# 13thISE_ver11.net
KiCad netlist of a schematic drawn in EAGLE
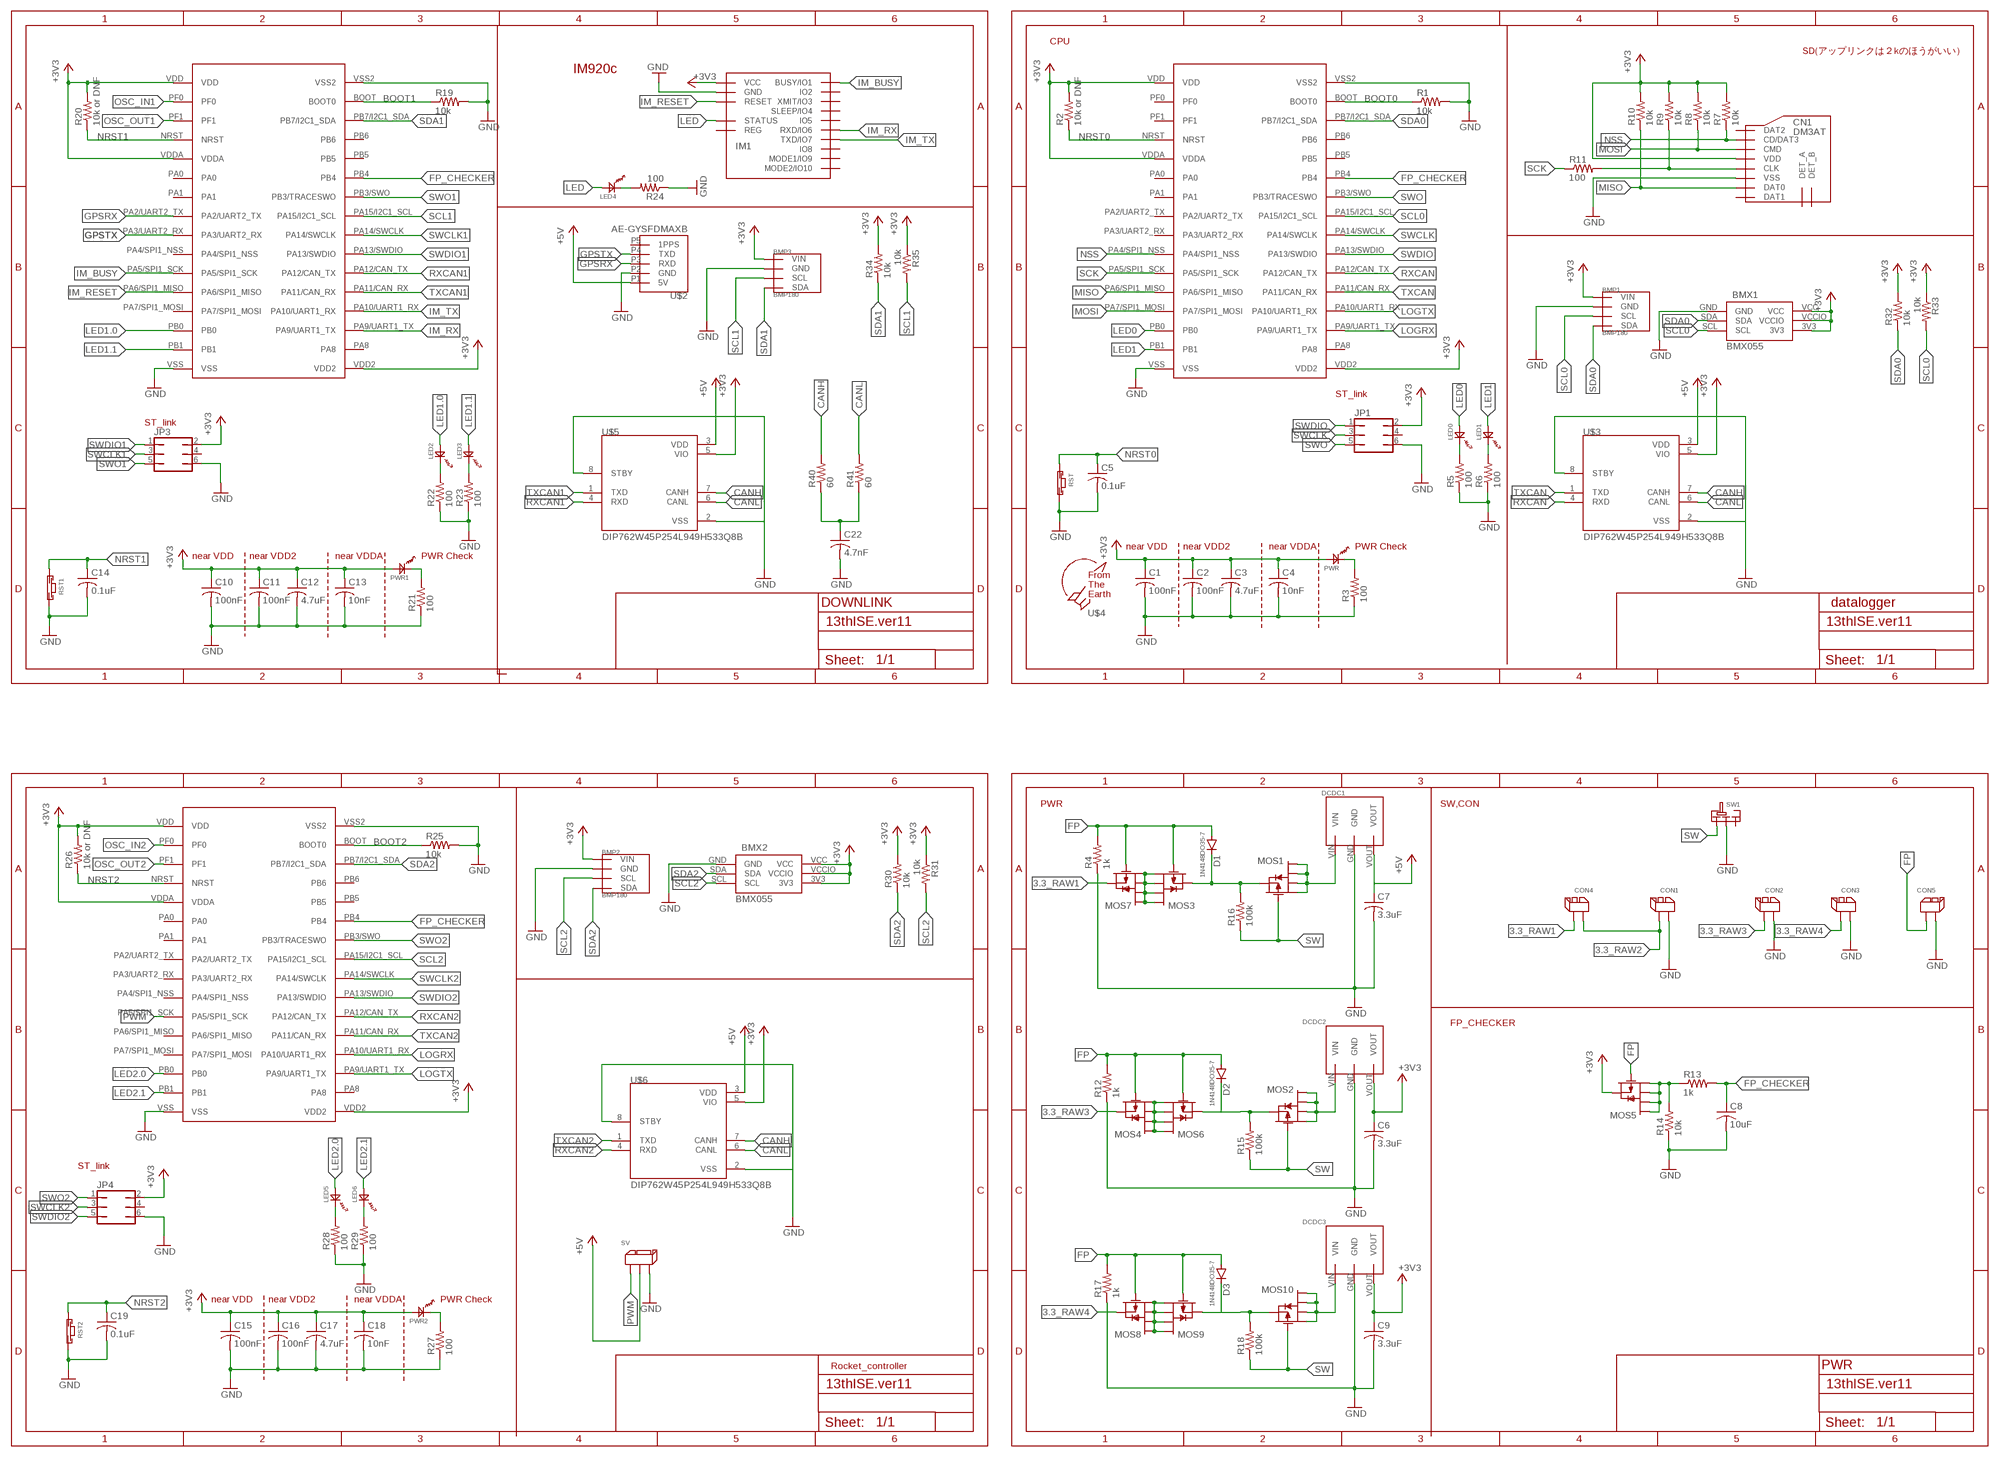
[diagram p0: schematic, sheet 1]

(export (version "E")
  (design (tool "Eeschema 10.0.6"))
  (components
    (comp (ref "BMP1")
      (value "BMP180")
      (footprint "eagle-import:GY-68")
      (libsource (lib "eagle-import") (part "BMP180"))
    )
    (comp (ref "BMP2")
      (value "BMP180")
      (footprint "eagle-import:GY-68")
      (libsource (lib "eagle-import") (part "BMP180"))
    )
    (comp (ref "BMP3")
      (value "BMP180")
      (footprint "eagle-import:GY-68")
      (libsource (lib "eagle-import") (part "BMP180"))
    )
    (comp (ref "BMX1")
      (value "BMX055")
      (footprint "eagle-import:BMX055")
      (libsource (lib "eagle-import") (part "BMX055"))
    )
    (comp (ref "BMX2")
      (value "BMX055")
      (footprint "eagle-import:BMX055")
      (libsource (lib "eagle-import") (part "BMX055"))
    )
    (comp (ref "C1")
      (value "100nF")
      (footprint "eagle-import:C1608")
      (libsource (lib "eagle-import") (part "C-USC1608"))
    )
    (comp (ref "C2")
      (value "100nF")
      (footprint "eagle-import:C1608")
      (libsource (lib "eagle-import") (part "C-USC1608"))
    )
    (comp (ref "C3")
      (value "4.7uF")
      (footprint "eagle-import:C1608")
      (libsource (lib "eagle-import") (part "C-USC1608"))
    )
    (comp (ref "C4")
      (value "10nF")
      (footprint "eagle-import:C1608")
      (libsource (lib "eagle-import") (part "C-USC1608"))
    )
    (comp (ref "C5")
      (value "0.1uF")
      (footprint "eagle-import:C1608")
      (libsource (lib "eagle-import") (part "C-USC1608"))
    )
    (comp (ref "C6")
      (value "3.3uF")
      (footprint "eagle-import:C0603")
      (libsource (lib "eagle-import") (part "C-USC0603"))
    )
    (comp (ref "C7")
      (value "3.3uF")
      (footprint "eagle-import:C0603")
      (libsource (lib "eagle-import") (part "C-USC0603"))
    )
    (comp (ref "C8")
      (value "10uF")
      (footprint "eagle-import:C0603")
      (libsource (lib "eagle-import") (part "C-USC0603"))
    )
    (comp (ref "C9")
      (value "3.3uF")
      (footprint "eagle-import:C0603")
      (libsource (lib "eagle-import") (part "C-USC0603"))
    )
    (comp (ref "C10")
      (value "100nF")
      (footprint "eagle-import:C1608")
      (libsource (lib "eagle-import") (part "C-USC1608"))
    )
    (comp (ref "C11")
      (value "100nF")
      (footprint "eagle-import:C1608")
      (libsource (lib "eagle-import") (part "C-USC1608"))
    )
    (comp (ref "C12")
      (value "4.7uF")
      (footprint "eagle-import:C1608")
      (libsource (lib "eagle-import") (part "C-USC1608"))
    )
    (comp (ref "C13")
      (value "10nF")
      (footprint "eagle-import:C1608")
      (libsource (lib "eagle-import") (part "C-USC1608"))
    )
    (comp (ref "C14")
      (value "0.1uF")
      (footprint "eagle-import:C1608")
      (libsource (lib "eagle-import") (part "C-USC1608"))
    )
    (comp (ref "C15")
      (value "100nF")
      (footprint "eagle-import:C1608")
      (libsource (lib "eagle-import") (part "C-USC1608"))
    )
    (comp (ref "C16")
      (value "100nF")
      (footprint "eagle-import:C1608")
      (libsource (lib "eagle-import") (part "C-USC1608"))
    )
    (comp (ref "C17")
      (value "4.7uF")
      (footprint "eagle-import:C1608")
      (libsource (lib "eagle-import") (part "C-USC1608"))
    )
    (comp (ref "C18")
      (value "10nF")
      (footprint "eagle-import:C1608")
      (libsource (lib "eagle-import") (part "C-USC1608"))
    )
    (comp (ref "C19")
      (value "0.1uF")
      (footprint "eagle-import:C1608")
      (libsource (lib "eagle-import") (part "C-USC1608"))
    )
    (comp (ref "C22")
      (value "4.7nF")
      (footprint "eagle-import:C0603")
      (libsource (lib "eagle-import") (part "C-USC0603"))
    )
    (comp (ref "CN1")
      (value "DM3AT")
      (footprint "eagle-import:DM3AT")
      (libsource (lib "eagle-import") (part "DM3AT"))
    )
    (comp (ref "CON1")
      (value "2PIN")
      (footprint "eagle-import:2PIN")
      (libsource (lib "eagle-import") (part "2PIN"))
    )
    (comp (ref "CON2")
      (value "2PIN")
      (footprint "eagle-import:2PIN")
      (libsource (lib "eagle-import") (part "2PIN"))
    )
    (comp (ref "CON3")
      (value "2PIN")
      (footprint "eagle-import:2PIN")
      (libsource (lib "eagle-import") (part "2PIN"))
    )
    (comp (ref "CON4")
      (value "2PIN")
      (footprint "eagle-import:2PIN")
      (libsource (lib "eagle-import") (part "2PIN"))
    )
    (comp (ref "CON5")
      (value "2PIN")
      (footprint "eagle-import:2PIN")
      (libsource (lib "eagle-import") (part "2PIN"))
    )
    (comp (ref "D1")
      (value "1N4148DO35-7")
      (footprint "eagle-import:DO35-7")
      (libsource (lib "eagle-import") (part "1N4148DO35-7"))
    )
    (comp (ref "D2")
      (value "1N4148DO35-7")
      (footprint "eagle-import:DO35-7")
      (libsource (lib "eagle-import") (part "1N4148DO35-7"))
    )
    (comp (ref "D3")
      (value "1N4148DO35-7")
      (footprint "eagle-import:DO35-7")
      (libsource (lib "eagle-import") (part "1N4148DO35-7"))
    )
    (comp (ref "DCDC1")
      (value "5V1A_M78AR05-1")
      (footprint "eagle-import:5V1A_M78AR05-1")
      (libsource (lib "eagle-import") (part "5V1A_M78AR05-1"))
    )
    (comp (ref "DCDC2")
      (value "3.3V1A_M78AR033-1")
      (footprint "eagle-import:3.3V1A_M78AR033-1")
      (libsource (lib "eagle-import") (part "3.3V1A_M78AR033-1"))
    )
    (comp (ref "DCDC3")
      (value "3.3V1A_M78AR033-1")
      (footprint "eagle-import:3.3V1A_M78AR033-1")
      (libsource (lib "eagle-import") (part "3.3V1A_M78AR033-1"))
    )
    (comp (ref "IM1")
      (value "IM920_IM920C")
      (footprint "eagle-import:IM920_IM920C")
      (libsource (lib "eagle-import") (part "IM920_IM920C"))
    )
    (comp (ref "JP1")
      (value "JP3Q")
      (footprint "eagle-import:JP3Q")
      (libsource (lib "eagle-import") (part "JP3Q"))
    )
    (comp (ref "JP3")
      (value "JP3Q")
      (footprint "eagle-import:JP3Q")
      (libsource (lib "eagle-import") (part "JP3Q"))
    )
    (comp (ref "JP4")
      (value "JP3Q")
      (footprint "eagle-import:JP3Q")
      (libsource (lib "eagle-import") (part "JP3Q"))
    )
    (comp (ref "LED0")
      (value "OSXX1608C1A")
      (footprint "eagle-import:OSXX1608C1A")
      (libsource (lib "eagle-import") (part "OSXX1608C1A"))
    )
    (comp (ref "LED1")
      (value "OSXX1608C1A")
      (footprint "eagle-import:OSXX1608C1A")
      (libsource (lib "eagle-import") (part "OSXX1608C1A"))
    )
    (comp (ref "LED2")
      (value "OSXX1608C1A")
      (footprint "eagle-import:OSXX1608C1A")
      (libsource (lib "eagle-import") (part "OSXX1608C1A"))
    )
    (comp (ref "LED3")
      (value "OSXX1608C1A")
      (footprint "eagle-import:OSXX1608C1A")
      (libsource (lib "eagle-import") (part "OSXX1608C1A"))
    )
    (comp (ref "LED4")
      (value "OSXX1608C1A")
      (footprint "eagle-import:OSXX1608C1A")
      (libsource (lib "eagle-import") (part "OSXX1608C1A"))
    )
    (comp (ref "LED5")
      (value "OSXX1608C1A")
      (footprint "eagle-import:OSXX1608C1A")
      (libsource (lib "eagle-import") (part "OSXX1608C1A"))
    )
    (comp (ref "LED6")
      (value "OSXX1608C1A")
      (footprint "eagle-import:OSXX1608C1A")
      (libsource (lib "eagle-import") (part "OSXX1608C1A"))
    )
    (comp (ref "MOS1")
      (value "PCH_SSM6J808R")
      (footprint "eagle-import:SSM6J808R")
      (libsource (lib "eagle-import") (part "PCH_SSM6J808R"))
    )
    (comp (ref "MOS2")
      (value "PCH_SSM6J808R")
      (footprint "eagle-import:SSM6J808R")
      (libsource (lib "eagle-import") (part "PCH_SSM6J808R"))
    )
    (comp (ref "MOS3")
      (value "PCH_SSM6J808R")
      (footprint "eagle-import:SSM6J808R")
      (libsource (lib "eagle-import") (part "PCH_SSM6J808R"))
    )
    (comp (ref "MOS4")
      (value "PCH_SSM6J808R")
      (footprint "eagle-import:SSM6J808R")
      (libsource (lib "eagle-import") (part "PCH_SSM6J808R"))
    )
    (comp (ref "MOS5")
      (value "PCH_SSM6J808R")
      (footprint "eagle-import:SSM6J808R")
      (libsource (lib "eagle-import") (part "PCH_SSM6J808R"))
    )
    (comp (ref "MOS6")
      (value "PCH_SSM6J808R")
      (footprint "eagle-import:SSM6J808R")
      (libsource (lib "eagle-import") (part "PCH_SSM6J808R"))
    )
    (comp (ref "MOS7")
      (value "PCH_SSM6J808R")
      (footprint "eagle-import:SSM6J808R")
      (libsource (lib "eagle-import") (part "PCH_SSM6J808R"))
    )
    (comp (ref "MOS8")
      (value "PCH_SSM6J808R")
      (footprint "eagle-import:SSM6J808R")
      (libsource (lib "eagle-import") (part "PCH_SSM6J808R"))
    )
    (comp (ref "MOS9")
      (value "PCH_SSM6J808R")
      (footprint "eagle-import:SSM6J808R")
      (libsource (lib "eagle-import") (part "PCH_SSM6J808R"))
    )
    (comp (ref "MOS10")
      (value "PCH_SSM6J808R")
      (footprint "eagle-import:SSM6J808R")
      (libsource (lib "eagle-import") (part "PCH_SSM6J808R"))
    )
    (comp (ref "PWR")
      (value "OSXX1608C1A")
      (footprint "eagle-import:OSXX1608C1A")
      (libsource (lib "eagle-import") (part "OSXX1608C1A"))
    )
    (comp (ref "PWR1")
      (value "OSXX1608C1A")
      (footprint "eagle-import:OSXX1608C1A")
      (libsource (lib "eagle-import") (part "OSXX1608C1A"))
    )
    (comp (ref "PWR2")
      (value "OSXX1608C1A")
      (footprint "eagle-import:OSXX1608C1A")
      (libsource (lib "eagle-import") (part "OSXX1608C1A"))
    )
    (comp (ref "R1")
      (value "10k")
      (footprint "eagle-import:R0603")
      (libsource (lib "eagle-import") (part "R-US_R0603"))
    )
    (comp (ref "R2")
      (value "10k or DNF")
      (footprint "eagle-import:R0603")
      (libsource (lib "eagle-import") (part "R-US_R0603"))
    )
    (comp (ref "R3")
      (value "100")
      (footprint "eagle-import:R0603")
      (libsource (lib "eagle-import") (part "R-US_R0603"))
    )
    (comp (ref "R4")
      (value "1k")
      (footprint "eagle-import:R0603")
      (libsource (lib "eagle-import") (part "R-US_R0603"))
    )
    (comp (ref "R5")
      (value "100")
      (footprint "eagle-import:R0603")
      (libsource (lib "eagle-import") (part "R-US_R0603"))
    )
    (comp (ref "R6")
      (value "100")
      (footprint "eagle-import:R0603")
      (libsource (lib "eagle-import") (part "R-US_R0603"))
    )
    (comp (ref "R7")
      (value "10k")
      (footprint "eagle-import:R0603")
      (libsource (lib "eagle-import") (part "R-US_R0603"))
    )
    (comp (ref "R8")
      (value "10k")
      (footprint "eagle-import:R0603")
      (libsource (lib "eagle-import") (part "R-US_R0603"))
    )
    (comp (ref "R9")
      (value "10k")
      (footprint "eagle-import:R0603")
      (libsource (lib "eagle-import") (part "R-US_R0603"))
    )
    (comp (ref "R10")
      (value "10k")
      (footprint "eagle-import:R0603")
      (libsource (lib "eagle-import") (part "R-US_R0603"))
    )
    (comp (ref "R11")
      (value "100")
      (footprint "eagle-import:R0603")
      (libsource (lib "eagle-import") (part "R-US_R0603"))
    )
    (comp (ref "R12")
      (value "1k")
      (footprint "eagle-import:R0603")
      (libsource (lib "eagle-import") (part "R-US_R0603"))
    )
    (comp (ref "R13")
      (value "1k")
      (footprint "eagle-import:R0603")
      (libsource (lib "eagle-import") (part "R-US_R0603"))
    )
    (comp (ref "R14")
      (value "10k")
      (footprint "eagle-import:R0603")
      (libsource (lib "eagle-import") (part "R-US_R0603"))
    )
    (comp (ref "R15")
      (value "100k")
      (footprint "eagle-import:R0603")
      (libsource (lib "eagle-import") (part "R-US_R0603"))
    )
    (comp (ref "R16")
      (value "100k")
      (footprint "eagle-import:R0603")
      (libsource (lib "eagle-import") (part "R-US_R0603"))
    )
    (comp (ref "R17")
      (value "1k")
      (footprint "eagle-import:R0603")
      (libsource (lib "eagle-import") (part "R-US_R0603"))
    )
    (comp (ref "R18")
      (value "100k")
      (footprint "eagle-import:R0603")
      (libsource (lib "eagle-import") (part "R-US_R0603"))
    )
    (comp (ref "R19")
      (value "10k")
      (footprint "eagle-import:R0603")
      (libsource (lib "eagle-import") (part "R-US_R0603"))
    )
    (comp (ref "R20")
      (value "10k or DNF")
      (footprint "eagle-import:R0603")
      (libsource (lib "eagle-import") (part "R-US_R0603"))
    )
    (comp (ref "R21")
      (value "100")
      (footprint "eagle-import:R0603")
      (libsource (lib "eagle-import") (part "R-US_R0603"))
    )
    (comp (ref "R22")
      (value "100")
      (footprint "eagle-import:R0603")
      (libsource (lib "eagle-import") (part "R-US_R0603"))
    )
    (comp (ref "R23")
      (value "100")
      (footprint "eagle-import:R0603")
      (libsource (lib "eagle-import") (part "R-US_R0603"))
    )
    (comp (ref "R24")
      (value "100")
      (footprint "eagle-import:R0603")
      (libsource (lib "eagle-import") (part "R-US_R0603"))
    )
    (comp (ref "R25")
      (value "10k")
      (footprint "eagle-import:R0603")
      (libsource (lib "eagle-import") (part "R-US_R0603"))
    )
    (comp (ref "R26")
      (value "10k or DNF")
      (footprint "eagle-import:R0603")
      (libsource (lib "eagle-import") (part "R-US_R0603"))
    )
    (comp (ref "R27")
      (value "100")
      (footprint "eagle-import:R0603")
      (libsource (lib "eagle-import") (part "R-US_R0603"))
    )
    (comp (ref "R28")
      (value "100")
      (footprint "eagle-import:R0603")
      (libsource (lib "eagle-import") (part "R-US_R0603"))
    )
    (comp (ref "R29")
      (value "100")
      (footprint "eagle-import:R0603")
      (libsource (lib "eagle-import") (part "R-US_R0603"))
    )
    (comp (ref "R30")
      (value "10k")
      (footprint "eagle-import:R0603")
      (libsource (lib "eagle-import") (part "R-US_R0603"))
    )
    (comp (ref "R31")
      (value "10k")
      (footprint "eagle-import:R0603")
      (libsource (lib "eagle-import") (part "R-US_R0603"))
    )
    (comp (ref "R32")
      (value "10k")
      (footprint "eagle-import:R0603")
      (libsource (lib "eagle-import") (part "R-US_R0603"))
    )
    (comp (ref "R33")
      (value "10k")
      (footprint "eagle-import:R0603")
      (libsource (lib "eagle-import") (part "R-US_R0603"))
    )
    (comp (ref "R34")
      (value "10k")
      (footprint "eagle-import:R0603")
      (libsource (lib "eagle-import") (part "R-US_R0603"))
    )
    (comp (ref "R35")
      (value "10k")
      (footprint "eagle-import:R0603")
      (libsource (lib "eagle-import") (part "R-US_R0603"))
    )
    (comp (ref "R40")
      (value "60")
      (footprint "eagle-import:R0603")
      (libsource (lib "eagle-import") (part "R-US_R0603"))
    )
    (comp (ref "R41")
      (value "60")
      (footprint "eagle-import:R0603")
      (libsource (lib "eagle-import") (part "R-US_R0603"))
    )
    (comp (ref "RST")
      (value "TVAF06-A020B-R")
      (footprint "eagle-import:TVAF06-A020B-R")
      (libsource (lib "eagle-import") (part "TVAF06-A020B-R"))
    )
    (comp (ref "RST1")
      (value "TVAF06-A020B-R")
      (footprint "eagle-import:TVAF06-A020B-R")
      (libsource (lib "eagle-import") (part "TVAF06-A020B-R"))
    )
    (comp (ref "RST2")
      (value "TVAF06-A020B-R")
      (footprint "eagle-import:TVAF06-A020B-R")
      (libsource (lib "eagle-import") (part "TVAF06-A020B-R"))
    )
    (comp (ref "STM0")
      (value "STM32F303K8")
      (footprint "eagle-import:STM32F303K8")
      (libsource (lib "eagle-import") (part "STM32F303K8"))
    )
    (comp (ref "STM1")
      (value "STM32F303K8")
      (footprint "eagle-import:STM32F303K8")
      (libsource (lib "eagle-import") (part "STM32F303K8"))
    )
    (comp (ref "SV")
      (value "3PIN")
      (footprint "eagle-import:3PIN")
      (libsource (lib "eagle-import") (part "3PIN"))
    )
    (comp (ref "SW1")
      (value "SRIDE_SWITCH")
      (footprint "eagle-import:SRIDE_SWITCH")
      (libsource (lib "eagle-import") (part "SRIDE_SWITCH"))
    )
    (comp (ref "U$1")
      (value "STM32F303K8")
      (footprint "eagle-import:STM32F303K8")
      (libsource (lib "eagle-import") (part "STM32F303K8"))
    )
    (comp (ref "U$2")
      (value "AE-GYSFDMAXB")
      (footprint "eagle-import:AE-GYSFDMAXB")
      (libsource (lib "eagle-import") (part "AE-GYSFDMAXB"))
    )
    (comp (ref "U$3")
      (value "DIP762W45P254L949H533Q8B")
      (footprint "eagle-import:DIP762W45P254L949H533Q8B")
      (libsource (lib "eagle-import") (part "DIP762W45P254L949H533Q8B"))
    )
    (comp (ref "U$4")
      (value "F.T.E.LOGO")
      (footprint "eagle-import:LOGO")
      (libsource (lib "eagle-import") (part "F.T.E.LOGO"))
    )
    (comp (ref "U$5")
      (value "DIP762W45P254L949H533Q8B")
      (footprint "eagle-import:DIP762W45P254L949H533Q8B")
      (libsource (lib "eagle-import") (part "DIP762W45P254L949H533Q8B"))
    )
    (comp (ref "U$6")
      (value "DIP762W45P254L949H533Q8B")
      (footprint "eagle-import:DIP762W45P254L949H533Q8B")
      (libsource (lib "eagle-import") (part "DIP762W45P254L949H533Q8B"))
    )
  )
  (nets
    (net (code "1") (name "+3V3") (class "Default")
      (node (ref "BMP1") (pin "P1") (pinfunction "VIN_P1") (pintype "bidirectional"))
      (node (ref "BMP2") (pin "P1") (pinfunction "VIN_P1") (pintype "bidirectional"))
      (node (ref "BMP3") (pin "P1") (pinfunction "VIN_P1") (pintype "bidirectional"))
      (node (ref "BMX1") (pin "3V3") (pinfunction "3V3_3V3") (pintype "power_in"))
      (node (ref "BMX1") (pin "VCC") (pinfunction "VCC_VCC") (pintype "power_in"))
      (node (ref "BMX1") (pin "VCCIO") (pinfunction "VCCIO_VCCIO") (pintype "power_in"))
      (node (ref "BMX2") (pin "3V3") (pinfunction "3V3_3V3") (pintype "power_in"))
      (node (ref "BMX2") (pin "VCC") (pinfunction "VCC_VCC") (pintype "power_in"))
      (node (ref "BMX2") (pin "VCCIO") (pinfunction "VCCIO_VCCIO") (pintype "power_in"))
      (node (ref "C1") (pin "1") (pinfunction "1_1") (pintype "passive"))
      (node (ref "C10") (pin "1") (pinfunction "1_1") (pintype "passive"))
      (node (ref "C11") (pin "1") (pinfunction "1_1") (pintype "passive"))
      (node (ref "C12") (pin "1") (pinfunction "1_1") (pintype "passive"))
      (node (ref "C13") (pin "1") (pinfunction "1_1") (pintype "passive"))
      (node (ref "C15") (pin "1") (pinfunction "1_1") (pintype "passive"))
      (node (ref "C16") (pin "1") (pinfunction "1_1") (pintype "passive"))
      (node (ref "C17") (pin "1") (pinfunction "1_1") (pintype "passive"))
      (node (ref "C18") (pin "1") (pinfunction "1_1") (pintype "passive"))
      (node (ref "C2") (pin "1") (pinfunction "1_1") (pintype "passive"))
      (node (ref "C3") (pin "1") (pinfunction "1_1") (pintype "passive"))
      (node (ref "C4") (pin "1") (pinfunction "1_1") (pintype "passive"))
      (node (ref "C6") (pin "1") (pinfunction "1_1") (pintype "passive"))
      (node (ref "C9") (pin "1") (pinfunction "1_1") (pintype "passive"))
      (node (ref "CN1") (pin "VDD") (pinfunction "VDD_VDD") (pintype "bidirectional"))
      (node (ref "DCDC2") (pin "VOUT") (pinfunction "VOUT_VOUT") (pintype "bidirectional"))
      (node (ref "DCDC3") (pin "VOUT") (pinfunction "VOUT_VOUT") (pintype "bidirectional"))
      (node (ref "IM1") (pin "$P17") (pinfunction "VCC_$P17") (pintype "bidirectional"))
      (node (ref "JP1") (pin "2") (pinfunction "2_2") (pintype "passive"))
      (node (ref "JP3") (pin "2") (pinfunction "2_2") (pintype "passive"))
      (node (ref "JP4") (pin "2") (pinfunction "2_2") (pintype "passive"))
      (node (ref "MOS5") (pin "4") (pinfunction "4_4") (pintype "bidirectional"))
      (node (ref "PWR") (pin "AN") (pinfunction "AN_AN") (pintype "bidirectional"))
      (node (ref "PWR1") (pin "AN") (pinfunction "AN_AN") (pintype "bidirectional"))
      (node (ref "PWR2") (pin "AN") (pinfunction "AN_AN") (pintype "bidirectional"))
      (node (ref "R10") (pin "2") (pinfunction "2_2") (pintype "passive"))
      (node (ref "R2") (pin "2") (pinfunction "2_2") (pintype "passive"))
      (node (ref "R20") (pin "2") (pinfunction "2_2") (pintype "passive"))
      (node (ref "R26") (pin "2") (pinfunction "2_2") (pintype "passive"))
      (node (ref "R30") (pin "2") (pinfunction "2_2") (pintype "passive"))
      (node (ref "R31") (pin "1") (pinfunction "1_1") (pintype "passive"))
      (node (ref "R32") (pin "2") (pinfunction "2_2") (pintype "passive"))
      (node (ref "R33") (pin "1") (pinfunction "1_1") (pintype "passive"))
      (node (ref "R34") (pin "2") (pinfunction "2_2") (pintype "passive"))
      (node (ref "R35") (pin "1") (pinfunction "1_1") (pintype "passive"))
      (node (ref "R7") (pin "2") (pinfunction "2_2") (pintype "passive"))
      (node (ref "R8") (pin "2") (pinfunction "2_2") (pintype "passive"))
      (node (ref "R9") (pin "2") (pinfunction "2_2") (pintype "passive"))
      (node (ref "STM0") (pin "VDD") (pinfunction "VDD_VDD") (pintype "power_in"))
      (node (ref "STM0") (pin "VDD2") (pinfunction "VDD2_VDD2") (pintype "power_in"))
      (node (ref "STM0") (pin "VDDA") (pinfunction "VDDA_VDDA") (pintype "power_in"))
      (node (ref "STM1") (pin "VDD") (pinfunction "VDD_VDD") (pintype "power_in"))
      (node (ref "STM1") (pin "VDD2") (pinfunction "VDD2_VDD2") (pintype "power_in"))
      (node (ref "STM1") (pin "VDDA") (pinfunction "VDDA_VDDA") (pintype "power_in"))
      (node (ref "U$1") (pin "VDD") (pinfunction "VDD_VDD") (pintype "power_in"))
      (node (ref "U$1") (pin "VDD2") (pinfunction "VDD2_VDD2") (pintype "power_in"))
      (node (ref "U$1") (pin "VDDA") (pinfunction "VDDA_VDDA") (pintype "power_in"))
      (node (ref "U$3") (pin "5") (pinfunction "VIO_5") (pintype "power_in"))
      (node (ref "U$5") (pin "5") (pinfunction "VIO_5") (pintype "power_in"))
      (node (ref "U$6") (pin "5") (pinfunction "VIO_5") (pintype "power_in"))
    )
    (net (code "2") (name "+5V") (class "Default")
      (node (ref "C7") (pin "1") (pinfunction "1_1") (pintype "passive"))
      (node (ref "DCDC1") (pin "VOUT") (pinfunction "VOUT_VOUT") (pintype "bidirectional"))
      (node (ref "SV") (pin "P$2") (pinfunction "P$2_P$2") (pintype "bidirectional"))
      (node (ref "U$2") (pin "P1") (pinfunction "5V_P1") (pintype "bidirectional"))
      (node (ref "U$3") (pin "3") (pinfunction "VDD_3") (pintype "power_in"))
      (node (ref "U$5") (pin "3") (pinfunction "VDD_3") (pintype "power_in"))
      (node (ref "U$6") (pin "3") (pinfunction "VDD_3") (pintype "power_in"))
    )
    (net (code "3") (name "/BOOT0") (class "Default")
      (node (ref "R1") (pin "1") (pinfunction "1_1") (pintype "passive"))
      (node (ref "STM0") (pin "BOOT") (pinfunction "BOOT0_BOOT") (pintype "bidirectional"))
    )
    (net (code "4") (name "/BOOT1") (class "Default")
      (node (ref "R19") (pin "1") (pinfunction "1_1") (pintype "passive"))
      (node (ref "STM1") (pin "BOOT") (pinfunction "BOOT0_BOOT") (pintype "bidirectional"))
    )
    (net (code "5") (name "/BOOT2") (class "Default")
      (node (ref "R25") (pin "1") (pinfunction "1_1") (pintype "passive"))
      (node (ref "U$1") (pin "BOOT") (pinfunction "BOOT0_BOOT") (pintype "bidirectional"))
    )
    (net (code "6") (name "3.3_RAW1") (class "Default")
      (node (ref "CON4") (pin "P$2") (pinfunction "P$2_P$2") (pintype "bidirectional"))
      (node (ref "MOS7") (pin "4") (pinfunction "4_4") (pintype "bidirectional"))
    )
    (net (code "7") (name "3.3_RAW2") (class "Default")
      (node (ref "CON1") (pin "P$2") (pinfunction "P$2_P$2") (pintype "bidirectional"))
      (node (ref "CON4") (pin "P$1") (pinfunction "P$1_P$1") (pintype "bidirectional"))
    )
    (net (code "8") (name "3.3_RAW3") (class "Default")
      (node (ref "CON2") (pin "P$2") (pinfunction "P$2_P$2") (pintype "bidirectional"))
      (node (ref "MOS4") (pin "4") (pinfunction "4_4") (pintype "bidirectional"))
    )
    (net (code "9") (name "3.3_RAW4") (class "Default")
      (node (ref "CON3") (pin "P$2") (pinfunction "P$2_P$2") (pintype "bidirectional"))
      (node (ref "MOS8") (pin "4") (pinfunction "4_4") (pintype "bidirectional"))
    )
    (net (code "10") (name "CANH") (class "Default")
      (node (ref "R40") (pin "2") (pinfunction "2_2") (pintype "passive"))
      (node (ref "U$3") (pin "7") (pinfunction "CANH_7") (pintype "bidirectional"))
      (node (ref "U$5") (pin "7") (pinfunction "CANH_7") (pintype "bidirectional"))
      (node (ref "U$6") (pin "7") (pinfunction "CANH_7") (pintype "bidirectional"))
    )
    (net (code "11") (name "CANL") (class "Default")
      (node (ref "R41") (pin "2") (pinfunction "2_2") (pintype "passive"))
      (node (ref "U$3") (pin "6") (pinfunction "CANL_6") (pintype "bidirectional"))
      (node (ref "U$5") (pin "6") (pinfunction "CANL_6") (pintype "bidirectional"))
      (node (ref "U$6") (pin "6") (pinfunction "CANL_6") (pintype "bidirectional"))
    )
    (net (code "12") (name "FP") (class "Default")
      (node (ref "CON5") (pin "P$1") (pinfunction "P$1_P$1") (pintype "bidirectional"))
      (node (ref "D1") (pin "A") (pinfunction "A_A") (pintype "passive"))
      (node (ref "D2") (pin "A") (pinfunction "A_A") (pintype "passive"))
      (node (ref "D3") (pin "A") (pinfunction "A_A") (pintype "passive"))
      (node (ref "MOS3") (pin "3") (pinfunction "3_3") (pintype "bidirectional"))
      (node (ref "MOS4") (pin "3") (pinfunction "3_3") (pintype "bidirectional"))
      (node (ref "MOS5") (pin "3") (pinfunction "3_3") (pintype "bidirectional"))
      (node (ref "MOS6") (pin "3") (pinfunction "3_3") (pintype "bidirectional"))
      (node (ref "MOS7") (pin "3") (pinfunction "3_3") (pintype "bidirectional"))
      (node (ref "MOS8") (pin "3") (pinfunction "3_3") (pintype "bidirectional"))
      (node (ref "MOS9") (pin "3") (pinfunction "3_3") (pintype "bidirectional"))
      (node (ref "R12") (pin "2") (pinfunction "2_2") (pintype "passive"))
      (node (ref "R17") (pin "2") (pinfunction "2_2") (pintype "passive"))
      (node (ref "R4") (pin "2") (pinfunction "2_2") (pintype "passive"))
    )
    (net (code "13") (name "FP_CHECKER") (class "Default")
      (node (ref "C8") (pin "1") (pinfunction "1_1") (pintype "passive"))
      (node (ref "R13") (pin "2") (pinfunction "2_2") (pintype "passive"))
      (node (ref "STM0") (pin "PB4") (pinfunction "PB4_PB4") (pintype "bidirectional"))
      (node (ref "STM1") (pin "PB4") (pinfunction "PB4_PB4") (pintype "bidirectional"))
      (node (ref "U$1") (pin "PB4") (pinfunction "PB4_PB4") (pintype "bidirectional"))
    )
    (net (code "14") (name "GND") (class "Default")
      (node (ref "BMP1") (pin "P2") (pinfunction "GND_P2") (pintype "bidirectional"))
      (node (ref "BMP2") (pin "P2") (pinfunction "GND_P2") (pintype "bidirectional"))
      (node (ref "BMP3") (pin "P2") (pinfunction "GND_P2") (pintype "bidirectional"))
      (node (ref "BMX1") (pin "GND") (pinfunction "GND_GND") (pintype "power_in"))
      (node (ref "BMX2") (pin "GND") (pinfunction "GND_GND") (pintype "power_in"))
      (node (ref "C1") (pin "2") (pinfunction "2_2") (pintype "passive"))
      (node (ref "C10") (pin "2") (pinfunction "2_2") (pintype "passive"))
      (node (ref "C11") (pin "2") (pinfunction "2_2") (pintype "passive"))
      (node (ref "C12") (pin "2") (pinfunction "2_2") (pintype "passive"))
      (node (ref "C13") (pin "2") (pinfunction "2_2") (pintype "passive"))
      (node (ref "C14") (pin "2") (pinfunction "2_2") (pintype "passive"))
      (node (ref "C15") (pin "2") (pinfunction "2_2") (pintype "passive"))
      (node (ref "C16") (pin "2") (pinfunction "2_2") (pintype "passive"))
      (node (ref "C17") (pin "2") (pinfunction "2_2") (pintype "passive"))
      (node (ref "C18") (pin "2") (pinfunction "2_2") (pintype "passive"))
      (node (ref "C19") (pin "2") (pinfunction "2_2") (pintype "passive"))
      (node (ref "C2") (pin "2") (pinfunction "2_2") (pintype "passive"))
      (node (ref "C22") (pin "2") (pinfunction "2_2") (pintype "passive"))
      (node (ref "C3") (pin "2") (pinfunction "2_2") (pintype "passive"))
      (node (ref "C4") (pin "2") (pinfunction "2_2") (pintype "passive"))
      (node (ref "C5") (pin "2") (pinfunction "2_2") (pintype "passive"))
      (node (ref "C6") (pin "2") (pinfunction "2_2") (pintype "passive"))
      (node (ref "C7") (pin "2") (pinfunction "2_2") (pintype "passive"))
      (node (ref "C8") (pin "2") (pinfunction "2_2") (pintype "passive"))
      (node (ref "C9") (pin "2") (pinfunction "2_2") (pintype "passive"))
      (node (ref "CN1") (pin "VSS") (pinfunction "VSS_VSS") (pintype "bidirectional"))
      (node (ref "CON1") (pin "P$1") (pinfunction "P$1_P$1") (pintype "bidirectional"))
      (node (ref "CON2") (pin "P$1") (pinfunction "P$1_P$1") (pintype "bidirectional"))
      (node (ref "CON3") (pin "P$1") (pinfunction "P$1_P$1") (pintype "bidirectional"))
      (node (ref "CON5") (pin "P$2") (pinfunction "P$2_P$2") (pintype "bidirectional"))
      (node (ref "DCDC1") (pin "GND") (pinfunction "GND_GND") (pintype "bidirectional"))
      (node (ref "DCDC2") (pin "GND") (pinfunction "GND_GND") (pintype "bidirectional"))
      (node (ref "DCDC3") (pin "GND") (pinfunction "GND_GND") (pintype "bidirectional"))
      (node (ref "IM1") (pin "$P18") (pinfunction "GND_$P18") (pintype "bidirectional"))
      (node (ref "JP1") (pin "6") (pinfunction "6_6") (pintype "passive"))
      (node (ref "JP3") (pin "6") (pinfunction "6_6") (pintype "passive"))
      (node (ref "JP4") (pin "6") (pinfunction "6_6") (pintype "passive"))
      (node (ref "R1") (pin "2") (pinfunction "2_2") (pintype "passive"))
      (node (ref "R12") (pin "1") (pinfunction "1_1") (pintype "passive"))
      (node (ref "R14") (pin "1") (pinfunction "1_1") (pintype "passive"))
      (node (ref "R17") (pin "1") (pinfunction "1_1") (pintype "passive"))
      (node (ref "R19") (pin "2") (pinfunction "2_2") (pintype "passive"))
      (node (ref "R21") (pin "1") (pinfunction "1_1") (pintype "passive"))
      (node (ref "R22") (pin "1") (pinfunction "1_1") (pintype "passive"))
      (node (ref "R23") (pin "1") (pinfunction "1_1") (pintype "passive"))
      (node (ref "R24") (pin "1") (pinfunction "1_1") (pintype "passive"))
      (node (ref "R25") (pin "2") (pinfunction "2_2") (pintype "passive"))
      (node (ref "R27") (pin "1") (pinfunction "1_1") (pintype "passive"))
      (node (ref "R28") (pin "1") (pinfunction "1_1") (pintype "passive"))
      (node (ref "R29") (pin "1") (pinfunction "1_1") (pintype "passive"))
      (node (ref "R3") (pin "1") (pinfunction "1_1") (pintype "passive"))
      (node (ref "R4") (pin "1") (pinfunction "1_1") (pintype "passive"))
      (node (ref "R5") (pin "1") (pinfunction "1_1") (pintype "passive"))
      (node (ref "R6") (pin "1") (pinfunction "1_1") (pintype "passive"))
      (node (ref "RST") (pin "P$2") (pinfunction "P$2_P$2") (pintype "bidirectional"))
      (node (ref "RST1") (pin "P$2") (pinfunction "P$2_P$2") (pintype "bidirectional"))
      (node (ref "RST2") (pin "P$2") (pinfunction "P$2_P$2") (pintype "bidirectional"))
      (node (ref "STM0") (pin "VSS") (pinfunction "VSS_VSS") (pintype "power_in"))
      (node (ref "STM0") (pin "VSS2") (pinfunction "VSS2_VSS2") (pintype "power_in"))
      (node (ref "STM1") (pin "VSS") (pinfunction "VSS_VSS") (pintype "power_in"))
      (node (ref "STM1") (pin "VSS2") (pinfunction "VSS2_VSS2") (pintype "power_in"))
      (node (ref "SV") (pin "P$3") (pinfunction "P$3_P$3") (pintype "bidirectional"))
      (node (ref "SW1") (pin "LR") (pinfunction "LR_LR") (pintype "bidirectional"))
      (node (ref "U$1") (pin "VSS") (pinfunction "VSS_VSS") (pintype "power_in"))
      (node (ref "U$1") (pin "VSS2") (pinfunction "VSS2_VSS2") (pintype "power_in"))
      (node (ref "U$2") (pin "P2") (pinfunction "GND_P2") (pintype "bidirectional"))
      (node (ref "U$3") (pin "2") (pinfunction "VSS_2") (pintype "power_in"))
      (node (ref "U$3") (pin "8") (pinfunction "STBY_8") (pintype "input"))
      (node (ref "U$5") (pin "2") (pinfunction "VSS_2") (pintype "power_in"))
      (node (ref "U$5") (pin "8") (pinfunction "STBY_8") (pintype "input"))
      (node (ref "U$6") (pin "2") (pinfunction "VSS_2") (pintype "power_in"))
      (node (ref "U$6") (pin "8") (pinfunction "STBY_8") (pintype "input"))
    )
    (net (code "15") (name "GPSRX") (class "Default")
      (node (ref "STM1") (pin "PA2/UART2_TX") (pinfunction "PA2/UART2_TX_PA2/UART2_TX") (pintype "bidirectional"))
      (node (ref "U$2") (pin "P3") (pinfunction "RXD_P3") (pintype "bidirectional"))
    )
    (net (code "16") (name "GPSTX") (class "Default")
      (node (ref "STM1") (pin "PA3/UART2_RX") (pinfunction "PA3/UART2_RX_PA3/UART2_RX") (pintype "bidirectional"))
      (node (ref "U$2") (pin "P4") (pinfunction "TXD_P4") (pintype "bidirectional"))
    )
    (net (code "17") (name "IM_BUSY") (class "Default")
      (node (ref "IM1") (pin "$P1") (pinfunction "BUSY/IO1_$P1") (pintype "bidirectional"))
      (node (ref "STM1") (pin "PA5/SPI1_SCK") (pinfunction "PA5/SPI1_SCK_PA5/SPI1_SCK") (pintype "bidirectional"))
    )
    (net (code "18") (name "IM_RESET") (class "Default")
      (node (ref "IM1") (pin "$P19") (pinfunction "RESET_$P19") (pintype "bidirectional"))
      (node (ref "STM1") (pin "PA6/SPI1_MISO") (pinfunction "PA6/SPI1_MISO_PA6/SPI1_MISO") (pintype "bidirectional"))
    )
    (net (code "19") (name "IM_RX") (class "Default")
      (node (ref "IM1") (pin "$P6") (pinfunction "RXD/IO6_$P6") (pintype "bidirectional"))
      (node (ref "STM1") (pin "PA9/UART1_TX") (pinfunction "PA9/UART1_TX_PA9/UART1_TX") (pintype "bidirectional"))
    )
    (net (code "20") (name "IM_TX") (class "Default")
      (node (ref "IM1") (pin "$P7") (pinfunction "TXD/IO7_$P7") (pintype "bidirectional"))
      (node (ref "STM1") (pin "PA10/UART1_RX") (pinfunction "PA10/UART1_RX_PA10/UART1_RX") (pintype "bidirectional"))
    )
    (net (code "21") (name "LED") (class "Default")
      (node (ref "IM1") (pin "$P15") (pinfunction "STATUS_$P15") (pintype "bidirectional"))
      (node (ref "LED4") (pin "AN") (pinfunction "AN_AN") (pintype "bidirectional"))
    )
    (net (code "22") (name "LED0") (class "Default")
      (node (ref "LED0") (pin "AN") (pinfunction "AN_AN") (pintype "bidirectional"))
      (node (ref "STM0") (pin "PB0") (pinfunction "PB0_PB0") (pintype "bidirectional"))
    )
    (net (code "23") (name "LED1") (class "Default")
      (node (ref "LED1") (pin "AN") (pinfunction "AN_AN") (pintype "bidirectional"))
      (node (ref "STM0") (pin "PB1") (pinfunction "PB1_PB1") (pintype "bidirectional"))
    )
    (net (code "24") (name "LED1.0") (class "Default")
      (node (ref "LED2") (pin "AN") (pinfunction "AN_AN") (pintype "bidirectional"))
      (node (ref "STM1") (pin "PB0") (pinfunction "PB0_PB0") (pintype "bidirectional"))
    )
    (net (code "25") (name "LED1.1") (class "Default")
      (node (ref "LED3") (pin "AN") (pinfunction "AN_AN") (pintype "bidirectional"))
      (node (ref "STM1") (pin "PB1") (pinfunction "PB1_PB1") (pintype "bidirectional"))
    )
    (net (code "26") (name "LED2.0") (class "Default")
      (node (ref "LED5") (pin "AN") (pinfunction "AN_AN") (pintype "bidirectional"))
      (node (ref "U$1") (pin "PB0") (pinfunction "PB0_PB0") (pintype "bidirectional"))
    )
    (net (code "27") (name "LED2.1") (class "Default")
      (node (ref "LED6") (pin "AN") (pinfunction "AN_AN") (pintype "bidirectional"))
      (node (ref "U$1") (pin "PB1") (pinfunction "PB1_PB1") (pintype "bidirectional"))
    )
    (net (code "28") (name "LOGRX") (class "Default")
      (node (ref "STM0") (pin "PA9/UART1_TX") (pinfunction "PA9/UART1_TX_PA9/UART1_TX") (pintype "bidirectional"))
      (node (ref "U$1") (pin "PA10/UART1_RX") (pinfunction "PA10/UART1_RX_PA10/UART1_RX") (pintype "bidirectional"))
    )
    (net (code "29") (name "LOGTX") (class "Default")
      (node (ref "STM0") (pin "PA10/UART1_RX") (pinfunction "PA10/UART1_RX_PA10/UART1_RX") (pintype "bidirectional"))
      (node (ref "U$1") (pin "PA9/UART1_TX") (pinfunction "PA9/UART1_TX_PA9/UART1_TX") (pintype "bidirectional"))
    )
    (net (code "30") (name "MISO") (class "Default")
      (node (ref "CN1") (pin "DAT0") (pinfunction "DAT0_DAT0") (pintype "bidirectional"))
      (node (ref "R10") (pin "1") (pinfunction "1_1") (pintype "passive"))
      (node (ref "STM0") (pin "PA6/SPI1_MISO") (pinfunction "PA6/SPI1_MISO_PA6/SPI1_MISO") (pintype "bidirectional"))
    )
    (net (code "31") (name "MOSI") (class "Default")
      (node (ref "CN1") (pin "CMD") (pinfunction "CMD_CMD") (pintype "bidirectional"))
      (node (ref "R8") (pin "1") (pinfunction "1_1") (pintype "passive"))
      (node (ref "STM0") (pin "PA7/SPI1_MOSI") (pinfunction "PA7/SPI1_MOSI_PA7/SPI1_MOSI") (pintype "bidirectional"))
    )
    (net (code "32") (name "NRST0") (class "Default")
      (node (ref "C5") (pin "1") (pinfunction "1_1") (pintype "passive"))
      (node (ref "R2") (pin "1") (pinfunction "1_1") (pintype "passive"))
      (node (ref "RST") (pin "P$1") (pinfunction "P$1_P$1") (pintype "bidirectional"))
      (node (ref "STM0") (pin "NRST") (pinfunction "NRST_NRST") (pintype "bidirectional"))
    )
    (net (code "33") (name "NRST1") (class "Default")
      (node (ref "C14") (pin "1") (pinfunction "1_1") (pintype "passive"))
      (node (ref "R20") (pin "1") (pinfunction "1_1") (pintype "passive"))
      (node (ref "RST1") (pin "P$1") (pinfunction "P$1_P$1") (pintype "bidirectional"))
      (node (ref "STM1") (pin "NRST") (pinfunction "NRST_NRST") (pintype "bidirectional"))
    )
    (net (code "34") (name "NRST2") (class "Default")
      (node (ref "C19") (pin "1") (pinfunction "1_1") (pintype "passive"))
      (node (ref "R26") (pin "1") (pinfunction "1_1") (pintype "passive"))
      (node (ref "RST2") (pin "P$1") (pinfunction "P$1_P$1") (pintype "bidirectional"))
      (node (ref "U$1") (pin "NRST") (pinfunction "NRST_NRST") (pintype "bidirectional"))
    )
    (net (code "35") (name "NSS") (class "Default")
      (node (ref "CN1") (pin "CD/DAT3") (pinfunction "CD/DAT3_CD/DAT3") (pintype "bidirectional"))
      (node (ref "R7") (pin "1") (pinfunction "1_1") (pintype "passive"))
      (node (ref "STM0") (pin "PA4/SPI1_NSS") (pinfunction "PA4/SPI1_NSS_PA4/SPI1_NSS") (pintype "bidirectional"))
    )
    (net (code "36") (name "Net-(C22-Pad1)") (class "Default")
      (node (ref "C22") (pin "1") (pinfunction "1_1") (pintype "passive"))
      (node (ref "R40") (pin "1") (pinfunction "1_1") (pintype "passive"))
      (node (ref "R41") (pin "1") (pinfunction "1_1") (pintype "passive"))
    )
    (net (code "37") (name "Net-(CN1-PadCLK)") (class "Default")
      (node (ref "CN1") (pin "CLK") (pinfunction "CLK_CLK") (pintype "bidirectional"))
      (node (ref "R11") (pin "2") (pinfunction "2_2") (pintype "passive"))
      (node (ref "R9") (pin "1") (pinfunction "1_1") (pintype "passive"))
    )
    (net (code "38") (name "Net-(D1-PadC)") (class "Default")
      (node (ref "D1") (pin "C") (pinfunction "C_C") (pintype "passive"))
      (node (ref "MOS1") (pin "4") (pinfunction "4_4") (pintype "bidirectional"))
      (node (ref "MOS3") (pin "4") (pinfunction "4_4") (pintype "bidirectional"))
      (node (ref "R16") (pin "2") (pinfunction "2_2") (pintype "passive"))
    )
    (net (code "39") (name "Net-(D2-PadC)") (class "Default")
      (node (ref "D2") (pin "C") (pinfunction "C_C") (pintype "passive"))
      (node (ref "MOS2") (pin "4") (pinfunction "4_4") (pintype "bidirectional"))
      (node (ref "MOS6") (pin "4") (pinfunction "4_4") (pintype "bidirectional"))
      (node (ref "R15") (pin "2") (pinfunction "2_2") (pintype "passive"))
    )
    (net (code "40") (name "Net-(D3-PadC)") (class "Default")
      (node (ref "D3") (pin "C") (pinfunction "C_C") (pintype "passive"))
      (node (ref "MOS10") (pin "4") (pinfunction "4_4") (pintype "bidirectional"))
      (node (ref "MOS9") (pin "4") (pinfunction "4_4") (pintype "bidirectional"))
      (node (ref "R18") (pin "2") (pinfunction "2_2") (pintype "passive"))
    )
    (net (code "41") (name "Net-(DCDC1-PadVIN)") (class "Default")
      (node (ref "DCDC1") (pin "VIN") (pinfunction "VIN_VIN") (pintype "bidirectional"))
      (node (ref "MOS1") (pin "1") (pinfunction "1_1") (pintype "bidirectional"))
      (node (ref "MOS1") (pin "2") (pinfunction "2_2") (pintype "bidirectional"))
      (node (ref "MOS1") (pin "5") (pinfunction "5_5") (pintype "bidirectional"))
      (node (ref "MOS1") (pin "6") (pinfunction "6_6") (pintype "bidirectional"))
    )
    (net (code "42") (name "Net-(DCDC2-PadVIN)") (class "Default")
      (node (ref "DCDC2") (pin "VIN") (pinfunction "VIN_VIN") (pintype "bidirectional"))
      (node (ref "MOS2") (pin "1") (pinfunction "1_1") (pintype "bidirectional"))
      (node (ref "MOS2") (pin "2") (pinfunction "2_2") (pintype "bidirectional"))
      (node (ref "MOS2") (pin "5") (pinfunction "5_5") (pintype "bidirectional"))
      (node (ref "MOS2") (pin "6") (pinfunction "6_6") (pintype "bidirectional"))
    )
    (net (code "43") (name "Net-(DCDC3-PadVIN)") (class "Default")
      (node (ref "DCDC3") (pin "VIN") (pinfunction "VIN_VIN") (pintype "bidirectional"))
      (node (ref "MOS10") (pin "1") (pinfunction "1_1") (pintype "bidirectional"))
      (node (ref "MOS10") (pin "2") (pinfunction "2_2") (pintype "bidirectional"))
      (node (ref "MOS10") (pin "5") (pinfunction "5_5") (pintype "bidirectional"))
      (node (ref "MOS10") (pin "6") (pinfunction "6_6") (pintype "bidirectional"))
    )
    (net (code "44") (name "Net-(LED0-PadCT)") (class "Default")
      (node (ref "LED0") (pin "CT") (pinfunction "CT_CT") (pintype "bidirectional"))
      (node (ref "R5") (pin "2") (pinfunction "2_2") (pintype "passive"))
    )
    (net (code "45") (name "Net-(LED1-PadCT)") (class "Default")
      (node (ref "LED1") (pin "CT") (pinfunction "CT_CT") (pintype "bidirectional"))
      (node (ref "R6") (pin "2") (pinfunction "2_2") (pintype "passive"))
    )
    (net (code "46") (name "Net-(LED2-PadCT)") (class "Default")
      (node (ref "LED2") (pin "CT") (pinfunction "CT_CT") (pintype "bidirectional"))
      (node (ref "R22") (pin "2") (pinfunction "2_2") (pintype "passive"))
    )
    (net (code "47") (name "Net-(LED3-PadCT)") (class "Default")
      (node (ref "LED3") (pin "CT") (pinfunction "CT_CT") (pintype "bidirectional"))
      (node (ref "R23") (pin "2") (pinfunction "2_2") (pintype "passive"))
    )
    (net (code "48") (name "Net-(LED4-PadCT)") (class "Default")
      (node (ref "LED4") (pin "CT") (pinfunction "CT_CT") (pintype "bidirectional"))
      (node (ref "R24") (pin "2") (pinfunction "2_2") (pintype "passive"))
    )
    (net (code "49") (name "Net-(LED5-PadCT)") (class "Default")
      (node (ref "LED5") (pin "CT") (pinfunction "CT_CT") (pintype "bidirectional"))
      (node (ref "R28") (pin "2") (pinfunction "2_2") (pintype "passive"))
    )
    (net (code "50") (name "Net-(LED6-PadCT)") (class "Default")
      (node (ref "LED6") (pin "CT") (pinfunction "CT_CT") (pintype "bidirectional"))
      (node (ref "R29") (pin "2") (pinfunction "2_2") (pintype "passive"))
    )
    (net (code "51") (name "Net-(MOS3-Pad1)") (class "Default")
      (node (ref "MOS3") (pin "1") (pinfunction "1_1") (pintype "bidirectional"))
      (node (ref "MOS3") (pin "2") (pinfunction "2_2") (pintype "bidirectional"))
      (node (ref "MOS3") (pin "5") (pinfunction "5_5") (pintype "bidirectional"))
      (node (ref "MOS3") (pin "6") (pinfunction "6_6") (pintype "bidirectional"))
      (node (ref "MOS7") (pin "1") (pinfunction "1_1") (pintype "bidirectional"))
      (node (ref "MOS7") (pin "2") (pinfunction "2_2") (pintype "bidirectional"))
      (node (ref "MOS7") (pin "5") (pinfunction "5_5") (pintype "bidirectional"))
      (node (ref "MOS7") (pin "6") (pinfunction "6_6") (pintype "bidirectional"))
    )
    (net (code "52") (name "Net-(MOS4-Pad1)") (class "Default")
      (node (ref "MOS4") (pin "1") (pinfunction "1_1") (pintype "bidirectional"))
      (node (ref "MOS4") (pin "2") (pinfunction "2_2") (pintype "bidirectional"))
      (node (ref "MOS4") (pin "5") (pinfunction "5_5") (pintype "bidirectional"))
      (node (ref "MOS4") (pin "6") (pinfunction "6_6") (pintype "bidirectional"))
      (node (ref "MOS6") (pin "1") (pinfunction "1_1") (pintype "bidirectional"))
      (node (ref "MOS6") (pin "2") (pinfunction "2_2") (pintype "bidirectional"))
      (node (ref "MOS6") (pin "5") (pinfunction "5_5") (pintype "bidirectional"))
      (node (ref "MOS6") (pin "6") (pinfunction "6_6") (pintype "bidirectional"))
    )
    (net (code "53") (name "Net-(MOS5-Pad1)") (class "Default")
      (node (ref "MOS5") (pin "1") (pinfunction "1_1") (pintype "bidirectional"))
      (node (ref "MOS5") (pin "2") (pinfunction "2_2") (pintype "bidirectional"))
      (node (ref "MOS5") (pin "5") (pinfunction "5_5") (pintype "bidirectional"))
      (node (ref "MOS5") (pin "6") (pinfunction "6_6") (pintype "bidirectional"))
      (node (ref "R13") (pin "1") (pinfunction "1_1") (pintype "passive"))
      (node (ref "R14") (pin "2") (pinfunction "2_2") (pintype "passive"))
    )
    (net (code "54") (name "Net-(MOS8-Pad1)") (class "Default")
      (node (ref "MOS8") (pin "1") (pinfunction "1_1") (pintype "bidirectional"))
      (node (ref "MOS8") (pin "2") (pinfunction "2_2") (pintype "bidirectional"))
      (node (ref "MOS8") (pin "5") (pinfunction "5_5") (pintype "bidirectional"))
      (node (ref "MOS8") (pin "6") (pinfunction "6_6") (pintype "bidirectional"))
      (node (ref "MOS9") (pin "1") (pinfunction "1_1") (pintype "bidirectional"))
      (node (ref "MOS9") (pin "2") (pinfunction "2_2") (pintype "bidirectional"))
      (node (ref "MOS9") (pin "5") (pinfunction "5_5") (pintype "bidirectional"))
      (node (ref "MOS9") (pin "6") (pinfunction "6_6") (pintype "bidirectional"))
    )
    (net (code "55") (name "Net-(PWR-PadCT)") (class "Default")
      (node (ref "PWR") (pin "CT") (pinfunction "CT_CT") (pintype "bidirectional"))
      (node (ref "R3") (pin "2") (pinfunction "2_2") (pintype "passive"))
    )
    (net (code "56") (name "Net-(PWR1-PadCT)") (class "Default")
      (node (ref "PWR1") (pin "CT") (pinfunction "CT_CT") (pintype "bidirectional"))
      (node (ref "R21") (pin "2") (pinfunction "2_2") (pintype "passive"))
    )
    (net (code "57") (name "Net-(PWR2-PadCT)") (class "Default")
      (node (ref "PWR2") (pin "CT") (pinfunction "CT_CT") (pintype "bidirectional"))
      (node (ref "R27") (pin "2") (pinfunction "2_2") (pintype "passive"))
    )
    (net (code "58") (name "OSC_IN1") (class "Default")
      (node (ref "STM1") (pin "PF0") (pinfunction "PF0_PF0") (pintype "bidirectional"))
    )
    (net (code "59") (name "OSC_IN2") (class "Default")
      (node (ref "U$1") (pin "PF0") (pinfunction "PF0_PF0") (pintype "bidirectional"))
    )
    (net (code "60") (name "OSC_OUT1") (class "Default")
      (node (ref "STM1") (pin "PF1") (pinfunction "PF1_PF1") (pintype "bidirectional"))
    )
    (net (code "61") (name "OSC_OUT2") (class "Default")
      (node (ref "U$1") (pin "PF1") (pinfunction "PF1_PF1") (pintype "bidirectional"))
    )
    (net (code "62") (name "PWM") (class "Default")
      (node (ref "SV") (pin "P$1") (pinfunction "P$1_P$1") (pintype "bidirectional"))
      (node (ref "U$1") (pin "PA5/SPI1_SCK") (pinfunction "PA5/SPI1_SCK_PA5/SPI1_SCK") (pintype "bidirectional"))
    )
    (net (code "63") (name "RXCAN") (class "Default")
      (node (ref "STM0") (pin "PA12/CAN_TX") (pinfunction "PA12/CAN_TX_PA12/CAN_TX") (pintype "bidirectional"))
      (node (ref "U$3") (pin "4") (pinfunction "RXD_4") (pintype "output"))
    )
    (net (code "64") (name "RXCAN1") (class "Default")
      (node (ref "STM1") (pin "PA12/CAN_TX") (pinfunction "PA12/CAN_TX_PA12/CAN_TX") (pintype "bidirectional"))
      (node (ref "U$5") (pin "4") (pinfunction "RXD_4") (pintype "output"))
    )
    (net (code "65") (name "RXCAN2") (class "Default")
      (node (ref "U$1") (pin "PA12/CAN_TX") (pinfunction "PA12/CAN_TX_PA12/CAN_TX") (pintype "bidirectional"))
      (node (ref "U$6") (pin "4") (pinfunction "RXD_4") (pintype "output"))
    )
    (net (code "66") (name "SCK") (class "Default")
      (node (ref "R11") (pin "1") (pinfunction "1_1") (pintype "passive"))
      (node (ref "STM0") (pin "PA5/SPI1_SCK") (pinfunction "PA5/SPI1_SCK_PA5/SPI1_SCK") (pintype "bidirectional"))
    )
    (net (code "67") (name "SCL0") (class "Default")
      (node (ref "BMP1") (pin "P3") (pinfunction "SCL_P3") (pintype "bidirectional"))
      (node (ref "BMX1") (pin "SCL") (pinfunction "SCL_SCL") (pintype "bidirectional"))
      (node (ref "R33") (pin "2") (pinfunction "2_2") (pintype "passive"))
      (node (ref "STM0") (pin "PA15/I2C1_SCL") (pinfunction "PA15/I2C1_SCL_PA15/I2C1_SCL") (pintype "bidirectional"))
    )
    (net (code "68") (name "SCL1") (class "Default")
      (node (ref "BMP3") (pin "P3") (pinfunction "SCL_P3") (pintype "bidirectional"))
      (node (ref "R35") (pin "2") (pinfunction "2_2") (pintype "passive"))
      (node (ref "STM1") (pin "PA15/I2C1_SCL") (pinfunction "PA15/I2C1_SCL_PA15/I2C1_SCL") (pintype "bidirectional"))
    )
    (net (code "69") (name "SCL2") (class "Default")
      (node (ref "BMP2") (pin "P3") (pinfunction "SCL_P3") (pintype "bidirectional"))
      (node (ref "BMX2") (pin "SCL") (pinfunction "SCL_SCL") (pintype "bidirectional"))
      (node (ref "R31") (pin "2") (pinfunction "2_2") (pintype "passive"))
      (node (ref "U$1") (pin "PA15/I2C1_SCL") (pinfunction "PA15/I2C1_SCL_PA15/I2C1_SCL") (pintype "bidirectional"))
    )
    (net (code "70") (name "SDA0") (class "Default")
      (node (ref "BMP1") (pin "P4") (pinfunction "SDA_P4") (pintype "bidirectional"))
      (node (ref "BMX1") (pin "SDA") (pinfunction "SDA_SDA") (pintype "bidirectional"))
      (node (ref "R32") (pin "1") (pinfunction "1_1") (pintype "passive"))
      (node (ref "STM0") (pin "PB7/I2C1_SDA") (pinfunction "PB7/I2C1_SDA_PB7/I2C1_SDA") (pintype "bidirectional"))
    )
    (net (code "71") (name "SDA1") (class "Default")
      (node (ref "BMP3") (pin "P4") (pinfunction "SDA_P4") (pintype "bidirectional"))
      (node (ref "R34") (pin "1") (pinfunction "1_1") (pintype "passive"))
      (node (ref "STM1") (pin "PB7/I2C1_SDA") (pinfunction "PB7/I2C1_SDA_PB7/I2C1_SDA") (pintype "bidirectional"))
    )
    (net (code "72") (name "SDA2") (class "Default")
      (node (ref "BMP2") (pin "P4") (pinfunction "SDA_P4") (pintype "bidirectional"))
      (node (ref "BMX2") (pin "SDA") (pinfunction "SDA_SDA") (pintype "bidirectional"))
      (node (ref "R30") (pin "1") (pinfunction "1_1") (pintype "passive"))
      (node (ref "U$1") (pin "PB7/I2C1_SDA") (pinfunction "PB7/I2C1_SDA_PB7/I2C1_SDA") (pintype "bidirectional"))
    )
    (net (code "73") (name "SW") (class "Default")
      (node (ref "MOS1") (pin "3") (pinfunction "3_3") (pintype "bidirectional"))
      (node (ref "MOS10") (pin "3") (pinfunction "3_3") (pintype "bidirectional"))
      (node (ref "MOS2") (pin "3") (pinfunction "3_3") (pintype "bidirectional"))
      (node (ref "R15") (pin "1") (pinfunction "1_1") (pintype "passive"))
      (node (ref "R16") (pin "1") (pinfunction "1_1") (pintype "passive"))
      (node (ref "R18") (pin "1") (pinfunction "1_1") (pintype "passive"))
      (node (ref "SW1") (pin "L") (pinfunction "L_L") (pintype "bidirectional"))
    )
    (net (code "74") (name "SWCLK") (class "Default")
      (node (ref "JP1") (pin "3") (pinfunction "3_3") (pintype "passive"))
      (node (ref "STM0") (pin "PA14/SWCLK") (pinfunction "PA14/SWCLK_PA14/SWCLK") (pintype "bidirectional"))
    )
    (net (code "75") (name "SWCLK1") (class "Default")
      (node (ref "JP3") (pin "3") (pinfunction "3_3") (pintype "passive"))
      (node (ref "STM1") (pin "PA14/SWCLK") (pinfunction "PA14/SWCLK_PA14/SWCLK") (pintype "bidirectional"))
    )
    (net (code "76") (name "SWCLK2") (class "Default")
      (node (ref "JP4") (pin "3") (pinfunction "3_3") (pintype "passive"))
      (node (ref "U$1") (pin "PA14/SWCLK") (pinfunction "PA14/SWCLK_PA14/SWCLK") (pintype "bidirectional"))
    )
    (net (code "77") (name "SWDIO") (class "Default")
      (node (ref "JP1") (pin "1") (pinfunction "1_1") (pintype "passive"))
      (node (ref "STM0") (pin "PA13/SWDIO") (pinfunction "PA13/SWDIO_PA13/SWDIO") (pintype "bidirectional"))
    )
    (net (code "78") (name "SWDIO1") (class "Default")
      (node (ref "JP3") (pin "1") (pinfunction "1_1") (pintype "passive"))
      (node (ref "STM1") (pin "PA13/SWDIO") (pinfunction "PA13/SWDIO_PA13/SWDIO") (pintype "bidirectional"))
    )
    (net (code "79") (name "SWDIO2") (class "Default")
      (node (ref "JP4") (pin "5") (pinfunction "5_5") (pintype "passive"))
      (node (ref "U$1") (pin "PA13/SWDIO") (pinfunction "PA13/SWDIO_PA13/SWDIO") (pintype "bidirectional"))
    )
    (net (code "80") (name "SWO") (class "Default")
      (node (ref "JP1") (pin "5") (pinfunction "5_5") (pintype "passive"))
      (node (ref "STM0") (pin "PB3/SWO") (pinfunction "PB3/TRACESWO_PB3/SWO") (pintype "bidirectional"))
    )
    (net (code "81") (name "SWO1") (class "Default")
      (node (ref "JP3") (pin "5") (pinfunction "5_5") (pintype "passive"))
      (node (ref "STM1") (pin "PB3/SWO") (pinfunction "PB3/TRACESWO_PB3/SWO") (pintype "bidirectional"))
    )
    (net (code "82") (name "SWO2") (class "Default")
      (node (ref "JP4") (pin "1") (pinfunction "1_1") (pintype "passive"))
      (node (ref "U$1") (pin "PB3/SWO") (pinfunction "PB3/TRACESWO_PB3/SWO") (pintype "bidirectional"))
    )
    (net (code "83") (name "TXCAN") (class "Default")
      (node (ref "STM0") (pin "PA11/CAN_RX") (pinfunction "PA11/CAN_RX_PA11/CAN_RX") (pintype "bidirectional"))
      (node (ref "U$3") (pin "1") (pinfunction "TXD_1") (pintype "input"))
    )
    (net (code "84") (name "TXCAN1") (class "Default")
      (node (ref "STM1") (pin "PA11/CAN_RX") (pinfunction "PA11/CAN_RX_PA11/CAN_RX") (pintype "bidirectional"))
      (node (ref "U$5") (pin "1") (pinfunction "TXD_1") (pintype "input"))
    )
    (net (code "85") (name "TXCAN2") (class "Default")
      (node (ref "U$1") (pin "PA11/CAN_RX") (pinfunction "PA11/CAN_RX_PA11/CAN_RX") (pintype "bidirectional"))
      (node (ref "U$6") (pin "1") (pinfunction "TXD_1") (pintype "input"))
    )
    (net (code "86") (name "unconnected-(CN1-PadDAT1)") (class "Default")
      (node (ref "CN1") (pin "DAT1") (pinfunction "DAT1_DAT1") (pintype "bidirectional"))
    )
    (net (code "87") (name "unconnected-(CN1-PadDAT2)") (class "Default")
      (node (ref "CN1") (pin "DAT2") (pinfunction "DAT2_DAT2") (pintype "bidirectional"))
    )
    (net (code "88") (name "unconnected-(CN1-PadDET_A)") (class "Default")
      (node (ref "CN1") (pin "DET_A") (pinfunction "DET_A_DET_A") (pintype "bidirectional"))
    )
    (net (code "89") (name "unconnected-(CN1-PadDET_B)") (class "Default")
      (node (ref "CN1") (pin "DET_B") (pinfunction "DET_B_DET_B") (pintype "bidirectional"))
    )
    (net (code "90") (name "unconnected-(IM1-IO2-Pad$P2)") (class "Default")
      (node (ref "IM1") (pin "$P2") (pinfunction "IO2_$P2") (pintype "bidirectional"))
    )
    (net (code "91") (name "unconnected-(IM1-IO5-Pad$P5)") (class "Default")
      (node (ref "IM1") (pin "$P5") (pinfunction "IO5_$P5") (pintype "bidirectional"))
    )
    (net (code "92") (name "unconnected-(IM1-IO8-Pad$P8)") (class "Default")
      (node (ref "IM1") (pin "$P8") (pinfunction "IO8_$P8") (pintype "bidirectional"))
    )
    (net (code "93") (name "unconnected-(IM1-MODE1{slash}IO9-Pad$P9)") (class "Default")
      (node (ref "IM1") (pin "$P9") (pinfunction "MODE1/IO9_$P9") (pintype "bidirectional"))
    )
    (net (code "94") (name "unconnected-(IM1-MODE2{slash}IO10-Pad$P10)") (class "Default")
      (node (ref "IM1") (pin "$P10") (pinfunction "MODE2/IO10_$P10") (pintype "bidirectional"))
    )
    (net (code "95") (name "unconnected-(IM1-REG-Pad$P16)") (class "Default")
      (node (ref "IM1") (pin "$P16") (pinfunction "REG_$P16") (pintype "bidirectional"))
    )
    (net (code "96") (name "unconnected-(IM1-SLEEP{slash}IO4-Pad$P4)") (class "Default")
      (node (ref "IM1") (pin "$P4") (pinfunction "SLEEP/IO4_$P4") (pintype "bidirectional"))
    )
    (net (code "97") (name "unconnected-(IM1-XMIT{slash}IO3-Pad$P3)") (class "Default")
      (node (ref "IM1") (pin "$P3") (pinfunction "XMIT/IO3_$P3") (pintype "bidirectional"))
    )
    (net (code "98") (name "unconnected-(JP1-Pad4)") (class "Default")
      (node (ref "JP1") (pin "4") (pinfunction "4_4") (pintype "passive"))
    )
    (net (code "99") (name "unconnected-(JP3-Pad4)") (class "Default")
      (node (ref "JP3") (pin "4") (pinfunction "4_4") (pintype "passive"))
    )
    (net (code "100") (name "unconnected-(JP4-Pad4)") (class "Default")
      (node (ref "JP4") (pin "4") (pinfunction "4_4") (pintype "passive"))
    )
    (net (code "101") (name "unconnected-(STM0-PadPA0)") (class "Default")
      (node (ref "STM0") (pin "PA0") (pinfunction "PA0_PA0") (pintype "bidirectional"))
    )
    (net (code "102") (name "unconnected-(STM0-PadPA1)") (class "Default")
      (node (ref "STM0") (pin "PA1") (pinfunction "PA1_PA1") (pintype "bidirectional"))
    )
    (net (code "103") (name "unconnected-(STM0-PadPA2{slash}UART2_TX)") (class "Default")
      (node (ref "STM0") (pin "PA2/UART2_TX") (pinfunction "PA2/UART2_TX_PA2/UART2_TX") (pintype "bidirectional"))
    )
    (net (code "104") (name "unconnected-(STM0-PadPA3{slash}UART2_RX)") (class "Default")
      (node (ref "STM0") (pin "PA3/UART2_RX") (pinfunction "PA3/UART2_RX_PA3/UART2_RX") (pintype "bidirectional"))
    )
    (net (code "105") (name "unconnected-(STM0-PadPA8)") (class "Default")
      (node (ref "STM0") (pin "PA8") (pinfunction "PA8_PA8") (pintype "bidirectional"))
    )
    (net (code "106") (name "unconnected-(STM0-PadPB5)") (class "Default")
      (node (ref "STM0") (pin "PB5") (pinfunction "PB5_PB5") (pintype "bidirectional"))
    )
    (net (code "107") (name "unconnected-(STM0-PadPB6)") (class "Default")
      (node (ref "STM0") (pin "PB6") (pinfunction "PB6_PB6") (pintype "bidirectional"))
    )
    (net (code "108") (name "unconnected-(STM0-PadPF0)") (class "Default")
      (node (ref "STM0") (pin "PF0") (pinfunction "PF0_PF0") (pintype "bidirectional"))
    )
    (net (code "109") (name "unconnected-(STM0-PadPF1)") (class "Default")
      (node (ref "STM0") (pin "PF1") (pinfunction "PF1_PF1") (pintype "bidirectional"))
    )
    (net (code "110") (name "unconnected-(STM1-PadPA0)") (class "Default")
      (node (ref "STM1") (pin "PA0") (pinfunction "PA0_PA0") (pintype "bidirectional"))
    )
    (net (code "111") (name "unconnected-(STM1-PadPA1)") (class "Default")
      (node (ref "STM1") (pin "PA1") (pinfunction "PA1_PA1") (pintype "bidirectional"))
    )
    (net (code "112") (name "unconnected-(STM1-PadPA4{slash}SPI1_NSS)") (class "Default")
      (node (ref "STM1") (pin "PA4/SPI1_NSS") (pinfunction "PA4/SPI1_NSS_PA4/SPI1_NSS") (pintype "bidirectional"))
    )
    (net (code "113") (name "unconnected-(STM1-PadPA7{slash}SPI1_MOSI)") (class "Default")
      (node (ref "STM1") (pin "PA7/SPI1_MOSI") (pinfunction "PA7/SPI1_MOSI_PA7/SPI1_MOSI") (pintype "bidirectional"))
    )
    (net (code "114") (name "unconnected-(STM1-PadPA8)") (class "Default")
      (node (ref "STM1") (pin "PA8") (pinfunction "PA8_PA8") (pintype "bidirectional"))
    )
    (net (code "115") (name "unconnected-(STM1-PadPB5)") (class "Default")
      (node (ref "STM1") (pin "PB5") (pinfunction "PB5_PB5") (pintype "bidirectional"))
    )
    (net (code "116") (name "unconnected-(STM1-PadPB6)") (class "Default")
      (node (ref "STM1") (pin "PB6") (pinfunction "PB6_PB6") (pintype "bidirectional"))
    )
    (net (code "117") (name "unconnected-(SW1-PadR)") (class "Default")
      (node (ref "SW1") (pin "R") (pinfunction "R_R") (pintype "bidirectional"))
    )
    (net (code "118") (name "unconnected-(U$1-PadPA0)") (class "Default")
      (node (ref "U$1") (pin "PA0") (pinfunction "PA0_PA0") (pintype "bidirectional"))
    )
    (net (code "119") (name "unconnected-(U$1-PadPA1)") (class "Default")
      (node (ref "U$1") (pin "PA1") (pinfunction "PA1_PA1") (pintype "bidirectional"))
    )
    (net (code "120") (name "unconnected-(U$1-PadPA2{slash}UART2_TX)") (class "Default")
      (node (ref "U$1") (pin "PA2/UART2_TX") (pinfunction "PA2/UART2_TX_PA2/UART2_TX") (pintype "bidirectional"))
    )
    (net (code "121") (name "unconnected-(U$1-PadPA3{slash}UART2_RX)") (class "Default")
      (node (ref "U$1") (pin "PA3/UART2_RX") (pinfunction "PA3/UART2_RX_PA3/UART2_RX") (pintype "bidirectional"))
    )
    (net (code "122") (name "unconnected-(U$1-PadPA4{slash}SPI1_NSS)") (class "Default")
      (node (ref "U$1") (pin "PA4/SPI1_NSS") (pinfunction "PA4/SPI1_NSS_PA4/SPI1_NSS") (pintype "bidirectional"))
    )
    (net (code "123") (name "unconnected-(U$1-PadPA6{slash}SPI1_MISO)") (class "Default")
      (node (ref "U$1") (pin "PA6/SPI1_MISO") (pinfunction "PA6/SPI1_MISO_PA6/SPI1_MISO") (pintype "bidirectional"))
    )
    (net (code "124") (name "unconnected-(U$1-PadPA7{slash}SPI1_MOSI)") (class "Default")
      (node (ref "U$1") (pin "PA7/SPI1_MOSI") (pinfunction "PA7/SPI1_MOSI_PA7/SPI1_MOSI") (pintype "bidirectional"))
    )
    (net (code "125") (name "unconnected-(U$1-PadPA8)") (class "Default")
      (node (ref "U$1") (pin "PA8") (pinfunction "PA8_PA8") (pintype "bidirectional"))
    )
    (net (code "126") (name "unconnected-(U$1-PadPB5)") (class "Default")
      (node (ref "U$1") (pin "PB5") (pinfunction "PB5_PB5") (pintype "bidirectional"))
    )
    (net (code "127") (name "unconnected-(U$1-PadPB6)") (class "Default")
      (node (ref "U$1") (pin "PB6") (pinfunction "PB6_PB6") (pintype "bidirectional"))
    )
    (net (code "128") (name "unconnected-(U$2-1PPS-PadP5)") (class "Default")
      (node (ref "U$2") (pin "P5") (pinfunction "1PPS_P5") (pintype "bidirectional"))
    )
  )
)
